# PiGI-V1_1.net
KiCad netlist of a schematic drawn in EAGLE
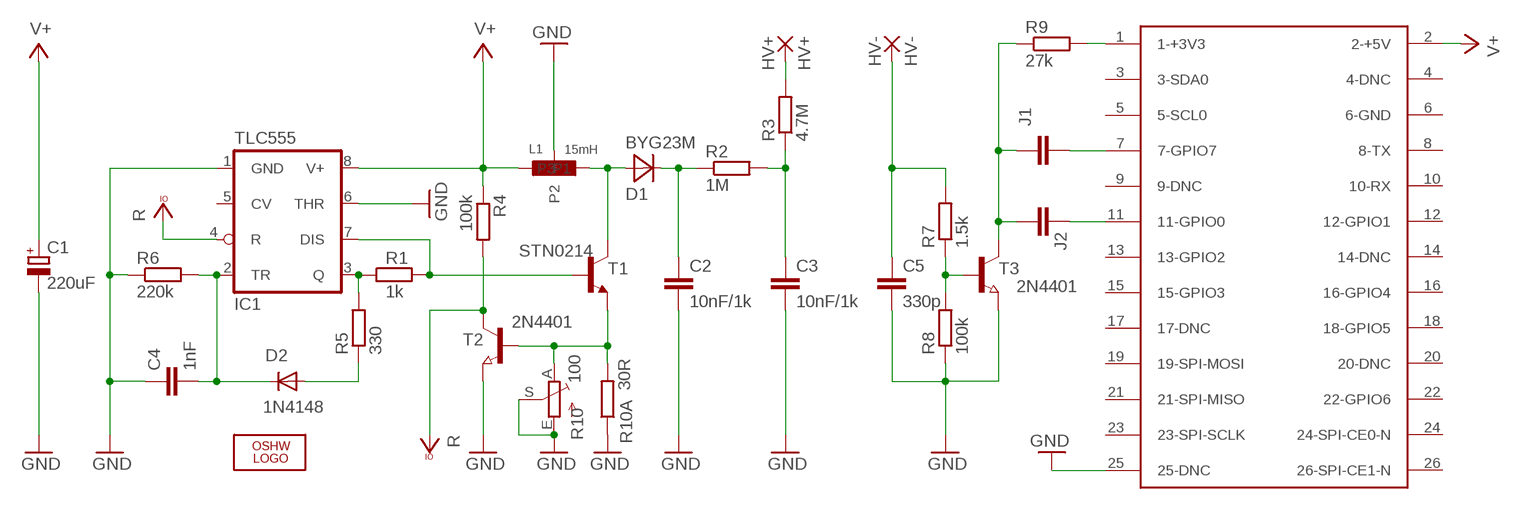
[diagram p0: schematic, sheet 1]

(export (version "E")
  (design (tool "Eeschema 10.0.6"))
  (components
    (comp (ref "C1")
      (value "220uF")
      (footprint "eagle-import:153CLV-0810")
      (libsource (lib "eagle-import") (part "CPOL-EU153CLV-0810"))
    )
    (comp (ref "C2")
      (value "10nF/1k")
      (footprint "eagle-import:C1206")
      (libsource (lib "eagle-import") (part "C-EUC1206"))
    )
    (comp (ref "C3")
      (value "10nF/1k")
      (footprint "eagle-import:C1206")
      (libsource (lib "eagle-import") (part "C-EUC1206"))
    )
    (comp (ref "C4")
      (value "1nF")
      (footprint "eagle-import:C0805")
      (libsource (lib "eagle-import") (part "C-EUC0805"))
    )
    (comp (ref "C5")
      (value "330p")
      (footprint "eagle-import:C0805")
      (libsource (lib "eagle-import") (part "C-EUC0805"))
    )
    (comp (ref "D1")
      (value "BYG23M")
      (footprint "eagle-import:SMA")
      (libsource (lib "eagle-import") (part "MBRA340T3"))
    )
    (comp (ref "D2")
      (value "1N4148")
      (footprint "eagle-import:SOD-123_MINI-SMA")
      (libsource (lib "eagle-import") (part "CGRM400-G1"))
    )
    (comp (ref "HV+")
      (value "HV+")
      (footprint "eagle-import:SMD2,54-5,08")
      (libsource (lib "eagle-import") (part "SMD5"))
    )
    (comp (ref "HV-")
      (value "HV-")
      (footprint "eagle-import:SMD2,54-5,08")
      (libsource (lib "eagle-import") (part "SMD5"))
    )
    (comp (ref "IC1")
      (value "TLC555")
      (footprint "eagle-import:SO08")
      (libsource (lib "eagle-import") (part "555DNE"))
    )
    (comp (ref "J1")
      (value "C-EUC0805")
      (footprint "eagle-import:C0805")
      (libsource (lib "eagle-import") (part "C-EUC0805"))
    )
    (comp (ref "J2")
      (value "C-EUC0805")
      (footprint "eagle-import:C0805")
      (libsource (lib "eagle-import") (part "C-EUC0805"))
    )
    (comp (ref "L1")
      (value "15mH")
      (footprint "eagle-import:1200LRS")
      (libsource (lib "eagle-import") (part "1200LRS"))
    )
    (comp (ref "LOGO1")
      (value "OSHW_LOGO_FILLX0150-NT")
      (footprint "eagle-import:OSHW_FILLX150_NOTEXT")
      (libsource (lib "eagle-import") (part "OSHW_LOGO_FILLX0150-NT"))
    )
    (comp (ref "PI-GIV1.0")
      (value "RASPBERRY-PI")
      (footprint "eagle-import:RASPBERRY-PI")
      (libsource (lib "eagle-import") (part "RASPBERRY-PI"))
    )
    (comp (ref "R1")
      (value "1k")
      (footprint "eagle-import:M0805")
      (libsource (lib "eagle-import") (part "R-EU_M0805"))
    )
    (comp (ref "R2")
      (value "1M")
      (footprint "eagle-import:R1206")
      (libsource (lib "eagle-import") (part "R-EU_R1206"))
    )
    (comp (ref "R3")
      (value "4.7M")
      (footprint "eagle-import:R1206")
      (libsource (lib "eagle-import") (part "R-EU_R1206"))
    )
    (comp (ref "R4")
      (value "100k")
      (footprint "eagle-import:R0805")
      (libsource (lib "eagle-import") (part "R-EU_R0805"))
    )
    (comp (ref "R5")
      (value "330")
      (footprint "eagle-import:R0805")
      (libsource (lib "eagle-import") (part "R-EU_R0805"))
    )
    (comp (ref "R6")
      (value "220k")
      (footprint "eagle-import:R0805")
      (libsource (lib "eagle-import") (part "R-EU_R0805"))
    )
    (comp (ref "R7")
      (value "1.5k")
      (footprint "eagle-import:R0805")
      (libsource (lib "eagle-import") (part "R-EU_R0805"))
    )
    (comp (ref "R8")
      (value "100k")
      (footprint "eagle-import:R0805")
      (libsource (lib "eagle-import") (part "R-EU_R0805"))
    )
    (comp (ref "R9")
      (value "27k")
      (footprint "eagle-import:R0805")
      (libsource (lib "eagle-import") (part "R-EU_R0805"))
    )
    (comp (ref "R10")
      (value "100")
      (footprint "eagle-import:RJ9W")
      (libsource (lib "eagle-import") (part "TRIM_EU-RJ9W"))
    )
    (comp (ref "R10A")
      (value "30R")
      (footprint "eagle-import:M0805")
      (libsource (lib "eagle-import") (part "R-EU_M0805"))
    )
    (comp (ref "T1")
      (value "STN0214")
      (footprint "eagle-import:SOT223")
      (libsource (lib "eagle-import") (part "-NPN-SOT223"))
    )
    (comp (ref "T2")
      (value "2N4401")
      (footprint "eagle-import:SOT23")
      (libsource (lib "eagle-import") (part "NPN-TRANSISTOR_SOT23"))
    )
    (comp (ref "T3")
      (value "2N4401")
      (footprint "eagle-import:SOT23")
      (libsource (lib "eagle-import") (part "NPN-TRANSISTOR_SOT23"))
    )
  )
  (nets
    (net (code "1") (name "GND") (class "Default")
      (node (ref "C1") (pin "-") (pinfunction "-_-") (pintype "passive"))
      (node (ref "C2") (pin "2") (pinfunction "2_2") (pintype "passive"))
      (node (ref "C3") (pin "2") (pinfunction "2_2") (pintype "passive"))
      (node (ref "C4") (pin "1") (pinfunction "1_1") (pintype "passive"))
      (node (ref "C5") (pin "2") (pinfunction "2_2") (pintype "passive"))
      (node (ref "IC1") (pin "1") (pinfunction "GND_1") (pintype "power_in"))
      (node (ref "IC1") (pin "6") (pinfunction "THR_6") (pintype "input"))
      (node (ref "L1") (pin "P4") (pinfunction "P2_P4") (pintype "bidirectional"))
      (node (ref "PI-GIV1.0") (pin "25") (pinfunction "25-DNC_25") (pintype "bidirectional"))
      (node (ref "R10") (pin "E") (pinfunction "A_E") (pintype "passive"))
      (node (ref "R10") (pin "S") (pinfunction "S_S") (pintype "passive"))
      (node (ref "R10A") (pin "1") (pinfunction "1_1") (pintype "passive"))
      (node (ref "R6") (pin "1") (pinfunction "1_1") (pintype "passive"))
      (node (ref "R8") (pin "1") (pinfunction "1_1") (pintype "passive"))
      (node (ref "T2") (pin "2") (pinfunction "E_2") (pintype "passive"))
      (node (ref "T3") (pin "2") (pinfunction "E_2") (pintype "passive"))
    )
    (net (code "2") (name "Net-(C2-Pad1)") (class "Default")
      (node (ref "C2") (pin "1") (pinfunction "1_1") (pintype "passive"))
      (node (ref "D1") (pin "C") (pinfunction "C_C") (pintype "passive"))
      (node (ref "R2") (pin "1") (pinfunction "1_1") (pintype "passive"))
    )
    (net (code "3") (name "Net-(C3-Pad1)") (class "Default")
      (node (ref "C3") (pin "1") (pinfunction "1_1") (pintype "passive"))
      (node (ref "R2") (pin "2") (pinfunction "2_2") (pintype "passive"))
      (node (ref "R3") (pin "1") (pinfunction "1_1") (pintype "passive"))
    )
    (net (code "4") (name "Net-(D2-PadA)") (class "Default")
      (node (ref "D2") (pin "A") (pinfunction "A_A") (pintype "passive"))
      (node (ref "R5") (pin "1") (pinfunction "1_1") (pintype "passive"))
    )
    (net (code "5") (name "Net-(HV+-P)") (class "Default")
      (node (ref "HV+") (pin "1") (pinfunction "P_1") (pintype "passive"))
      (node (ref "R3") (pin "2") (pinfunction "2_2") (pintype "passive"))
    )
    (net (code "6") (name "Net-(HV--P)") (class "Default")
      (node (ref "C5") (pin "1") (pinfunction "1_1") (pintype "passive"))
      (node (ref "HV-") (pin "1") (pinfunction "P_1") (pintype "passive"))
      (node (ref "R7") (pin "2") (pinfunction "2_2") (pintype "passive"))
    )
    (net (code "7") (name "Net-(IC1-DIS)") (class "Default")
      (node (ref "IC1") (pin "7") (pinfunction "DIS_7") (pintype "input"))
      (node (ref "R1") (pin "2") (pinfunction "2_2") (pintype "passive"))
      (node (ref "T1") (pin "1") (pinfunction "B_1") (pintype "passive"))
    )
    (net (code "8") (name "Net-(IC1-Q)") (class "Default")
      (node (ref "IC1") (pin "3") (pinfunction "Q_3") (pintype "output"))
      (node (ref "R1") (pin "1") (pinfunction "1_1") (pintype "passive"))
      (node (ref "R5") (pin "2") (pinfunction "2_2") (pintype "passive"))
    )
    (net (code "9") (name "Net-(IC1-TR)") (class "Default")
      (node (ref "C4") (pin "2") (pinfunction "2_2") (pintype "passive"))
      (node (ref "D2") (pin "C") (pinfunction "C_C") (pintype "passive"))
      (node (ref "IC1") (pin "2") (pinfunction "TR_2") (pintype "input"))
      (node (ref "R6") (pin "2") (pinfunction "2_2") (pintype "passive"))
    )
    (net (code "10") (name "Net-(PI-GIV1.0-1-+3V3)") (class "Default")
      (node (ref "PI-GIV1.0") (pin "1") (pinfunction "1-+3V3_1") (pintype "bidirectional"))
      (node (ref "R9") (pin "2") (pinfunction "2_2") (pintype "passive"))
    )
    (net (code "11") (name "Net-(PI-GIV1.0-7-GPIO7)") (class "Default")
      (node (ref "J1") (pin "1") (pinfunction "1_1") (pintype "passive"))
      (node (ref "PI-GIV1.0") (pin "7") (pinfunction "7-GPIO7_7") (pintype "bidirectional"))
    )
    (net (code "12") (name "Net-(PI-GIV1.0-11-GPIO0)") (class "Default")
      (node (ref "J2") (pin "1") (pinfunction "1_1") (pintype "passive"))
      (node (ref "PI-GIV1.0") (pin "11") (pinfunction "11-GPIO0_11") (pintype "bidirectional"))
    )
    (net (code "13") (name "Net-(R10-E)") (class "Default")
      (node (ref "R10") (pin "A") (pinfunction "E_A") (pintype "passive"))
      (node (ref "R10A") (pin "2") (pinfunction "2_2") (pintype "passive"))
      (node (ref "T1") (pin "3") (pinfunction "E_3") (pintype "passive"))
      (node (ref "T2") (pin "1") (pinfunction "B_1") (pintype "passive"))
    )
    (net (code "14") (name "Net-(T1-C)") (class "Default")
      (node (ref "D1") (pin "A") (pinfunction "A_A") (pintype "passive"))
      (node (ref "L1") (pin "P3") (pinfunction "P3_P3") (pintype "bidirectional"))
      (node (ref "T1") (pin "4") (pinfunction "C_4") (pintype "passive"))
    )
    (net (code "15") (name "Net-(T3-B)") (class "Default")
      (node (ref "R7") (pin "1") (pinfunction "1_1") (pintype "passive"))
      (node (ref "R8") (pin "2") (pinfunction "2_2") (pintype "passive"))
      (node (ref "T3") (pin "1") (pinfunction "B_1") (pintype "passive"))
    )
    (net (code "16") (name "Net-(T3-C)") (class "Default")
      (node (ref "J1") (pin "2") (pinfunction "2_2") (pintype "passive"))
      (node (ref "J2") (pin "2") (pinfunction "2_2") (pintype "passive"))
      (node (ref "R9") (pin "1") (pinfunction "1_1") (pintype "passive"))
      (node (ref "T3") (pin "3") (pinfunction "C_3") (pintype "passive"))
    )
    (net (code "17") (name "R") (class "Default")
      (node (ref "IC1") (pin "4") (pinfunction "R_4") (pintype "input"))
      (node (ref "R4") (pin "2") (pinfunction "2_2") (pintype "passive"))
      (node (ref "T2") (pin "3") (pinfunction "C_3") (pintype "passive"))
    )
    (net (code "18") (name "V+") (class "Default")
      (node (ref "C1") (pin "+") (pinfunction "+_+") (pintype "passive"))
      (node (ref "IC1") (pin "8") (pinfunction "V+_8") (pintype "power_in"))
      (node (ref "L1") (pin "P1") (pinfunction "P1_P1") (pintype "bidirectional"))
      (node (ref "PI-GIV1.0") (pin "2") (pinfunction "2-+5V_2") (pintype "bidirectional"))
      (node (ref "R4") (pin "1") (pinfunction "1_1") (pintype "passive"))
    )
    (net (code "19") (name "unconnected-(IC1-CV-Pad5)") (class "Default")
      (node (ref "IC1") (pin "5") (pinfunction "CV_5") (pintype "input"))
    )
    (net (code "20") (name "unconnected-(PI-GIV1.0-3-SDA0-Pad3)") (class "Default")
      (node (ref "PI-GIV1.0") (pin "3") (pinfunction "3-SDA0_3") (pintype "bidirectional"))
    )
    (net (code "21") (name "unconnected-(PI-GIV1.0-4-DNC-Pad4)") (class "Default")
      (node (ref "PI-GIV1.0") (pin "4") (pinfunction "4-DNC_4") (pintype "bidirectional"))
    )
    (net (code "22") (name "unconnected-(PI-GIV1.0-5-SCL0-Pad5)") (class "Default")
      (node (ref "PI-GIV1.0") (pin "5") (pinfunction "5-SCL0_5") (pintype "bidirectional"))
    )
    (net (code "23") (name "unconnected-(PI-GIV1.0-6-GND-Pad6)") (class "Default")
      (node (ref "PI-GIV1.0") (pin "6") (pinfunction "6-GND_6") (pintype "bidirectional"))
    )
    (net (code "24") (name "unconnected-(PI-GIV1.0-8-TX-Pad8)") (class "Default")
      (node (ref "PI-GIV1.0") (pin "8") (pinfunction "8-TX_8") (pintype "bidirectional"))
    )
    (net (code "25") (name "unconnected-(PI-GIV1.0-9-DNC-Pad9)") (class "Default")
      (node (ref "PI-GIV1.0") (pin "9") (pinfunction "9-DNC_9") (pintype "bidirectional"))
    )
    (net (code "26") (name "unconnected-(PI-GIV1.0-10-RX-Pad10)") (class "Default")
      (node (ref "PI-GIV1.0") (pin "10") (pinfunction "10-RX_10") (pintype "bidirectional"))
    )
    (net (code "27") (name "unconnected-(PI-GIV1.0-12-GPIO1-Pad12)") (class "Default")
      (node (ref "PI-GIV1.0") (pin "12") (pinfunction "12-GPIO1_12") (pintype "bidirectional"))
    )
    (net (code "28") (name "unconnected-(PI-GIV1.0-13-GPIO2-Pad13)") (class "Default")
      (node (ref "PI-GIV1.0") (pin "13") (pinfunction "13-GPIO2_13") (pintype "bidirectional"))
    )
    (net (code "29") (name "unconnected-(PI-GIV1.0-14-DNC-Pad14)") (class "Default")
      (node (ref "PI-GIV1.0") (pin "14") (pinfunction "14-DNC_14") (pintype "bidirectional"))
    )
    (net (code "30") (name "unconnected-(PI-GIV1.0-15-GPIO3-Pad15)") (class "Default")
      (node (ref "PI-GIV1.0") (pin "15") (pinfunction "15-GPIO3_15") (pintype "bidirectional"))
    )
    (net (code "31") (name "unconnected-(PI-GIV1.0-16-GPIO4-Pad16)") (class "Default")
      (node (ref "PI-GIV1.0") (pin "16") (pinfunction "16-GPIO4_16") (pintype "bidirectional"))
    )
    (net (code "32") (name "unconnected-(PI-GIV1.0-17-DNC-Pad17)") (class "Default")
      (node (ref "PI-GIV1.0") (pin "17") (pinfunction "17-DNC_17") (pintype "bidirectional"))
    )
    (net (code "33") (name "unconnected-(PI-GIV1.0-18-GPIO5-Pad18)") (class "Default")
      (node (ref "PI-GIV1.0") (pin "18") (pinfunction "18-GPIO5_18") (pintype "bidirectional"))
    )
    (net (code "34") (name "unconnected-(PI-GIV1.0-19-SPI-MOSI-Pad19)") (class "Default")
      (node (ref "PI-GIV1.0") (pin "19") (pinfunction "19-SPI-MOSI_19") (pintype "bidirectional"))
    )
    (net (code "35") (name "unconnected-(PI-GIV1.0-20-DNC-Pad20)") (class "Default")
      (node (ref "PI-GIV1.0") (pin "20") (pinfunction "20-DNC_20") (pintype "bidirectional"))
    )
    (net (code "36") (name "unconnected-(PI-GIV1.0-21-SPI-MISO-Pad21)") (class "Default")
      (node (ref "PI-GIV1.0") (pin "21") (pinfunction "21-SPI-MISO_21") (pintype "bidirectional"))
    )
    (net (code "37") (name "unconnected-(PI-GIV1.0-22-GPIO6-Pad22)") (class "Default")
      (node (ref "PI-GIV1.0") (pin "22") (pinfunction "22-GPIO6_22") (pintype "bidirectional"))
    )
    (net (code "38") (name "unconnected-(PI-GIV1.0-23-SPI-SCLK-Pad23)") (class "Default")
      (node (ref "PI-GIV1.0") (pin "23") (pinfunction "23-SPI-SCLK_23") (pintype "bidirectional"))
    )
    (net (code "39") (name "unconnected-(PI-GIV1.0-24-SPI-CE0-N-Pad24)") (class "Default")
      (node (ref "PI-GIV1.0") (pin "24") (pinfunction "24-SPI-CE0-N_24") (pintype "bidirectional"))
    )
    (net (code "40") (name "unconnected-(PI-GIV1.0-26-SPI-CE1-N-Pad26)") (class "Default")
      (node (ref "PI-GIV1.0") (pin "26") (pinfunction "26-SPI-CE1-N_26") (pintype "bidirectional"))
    )
  )
)
